# PCB_Sheet1.net
KiCad netlist of a schematic drawn in Altium Designer
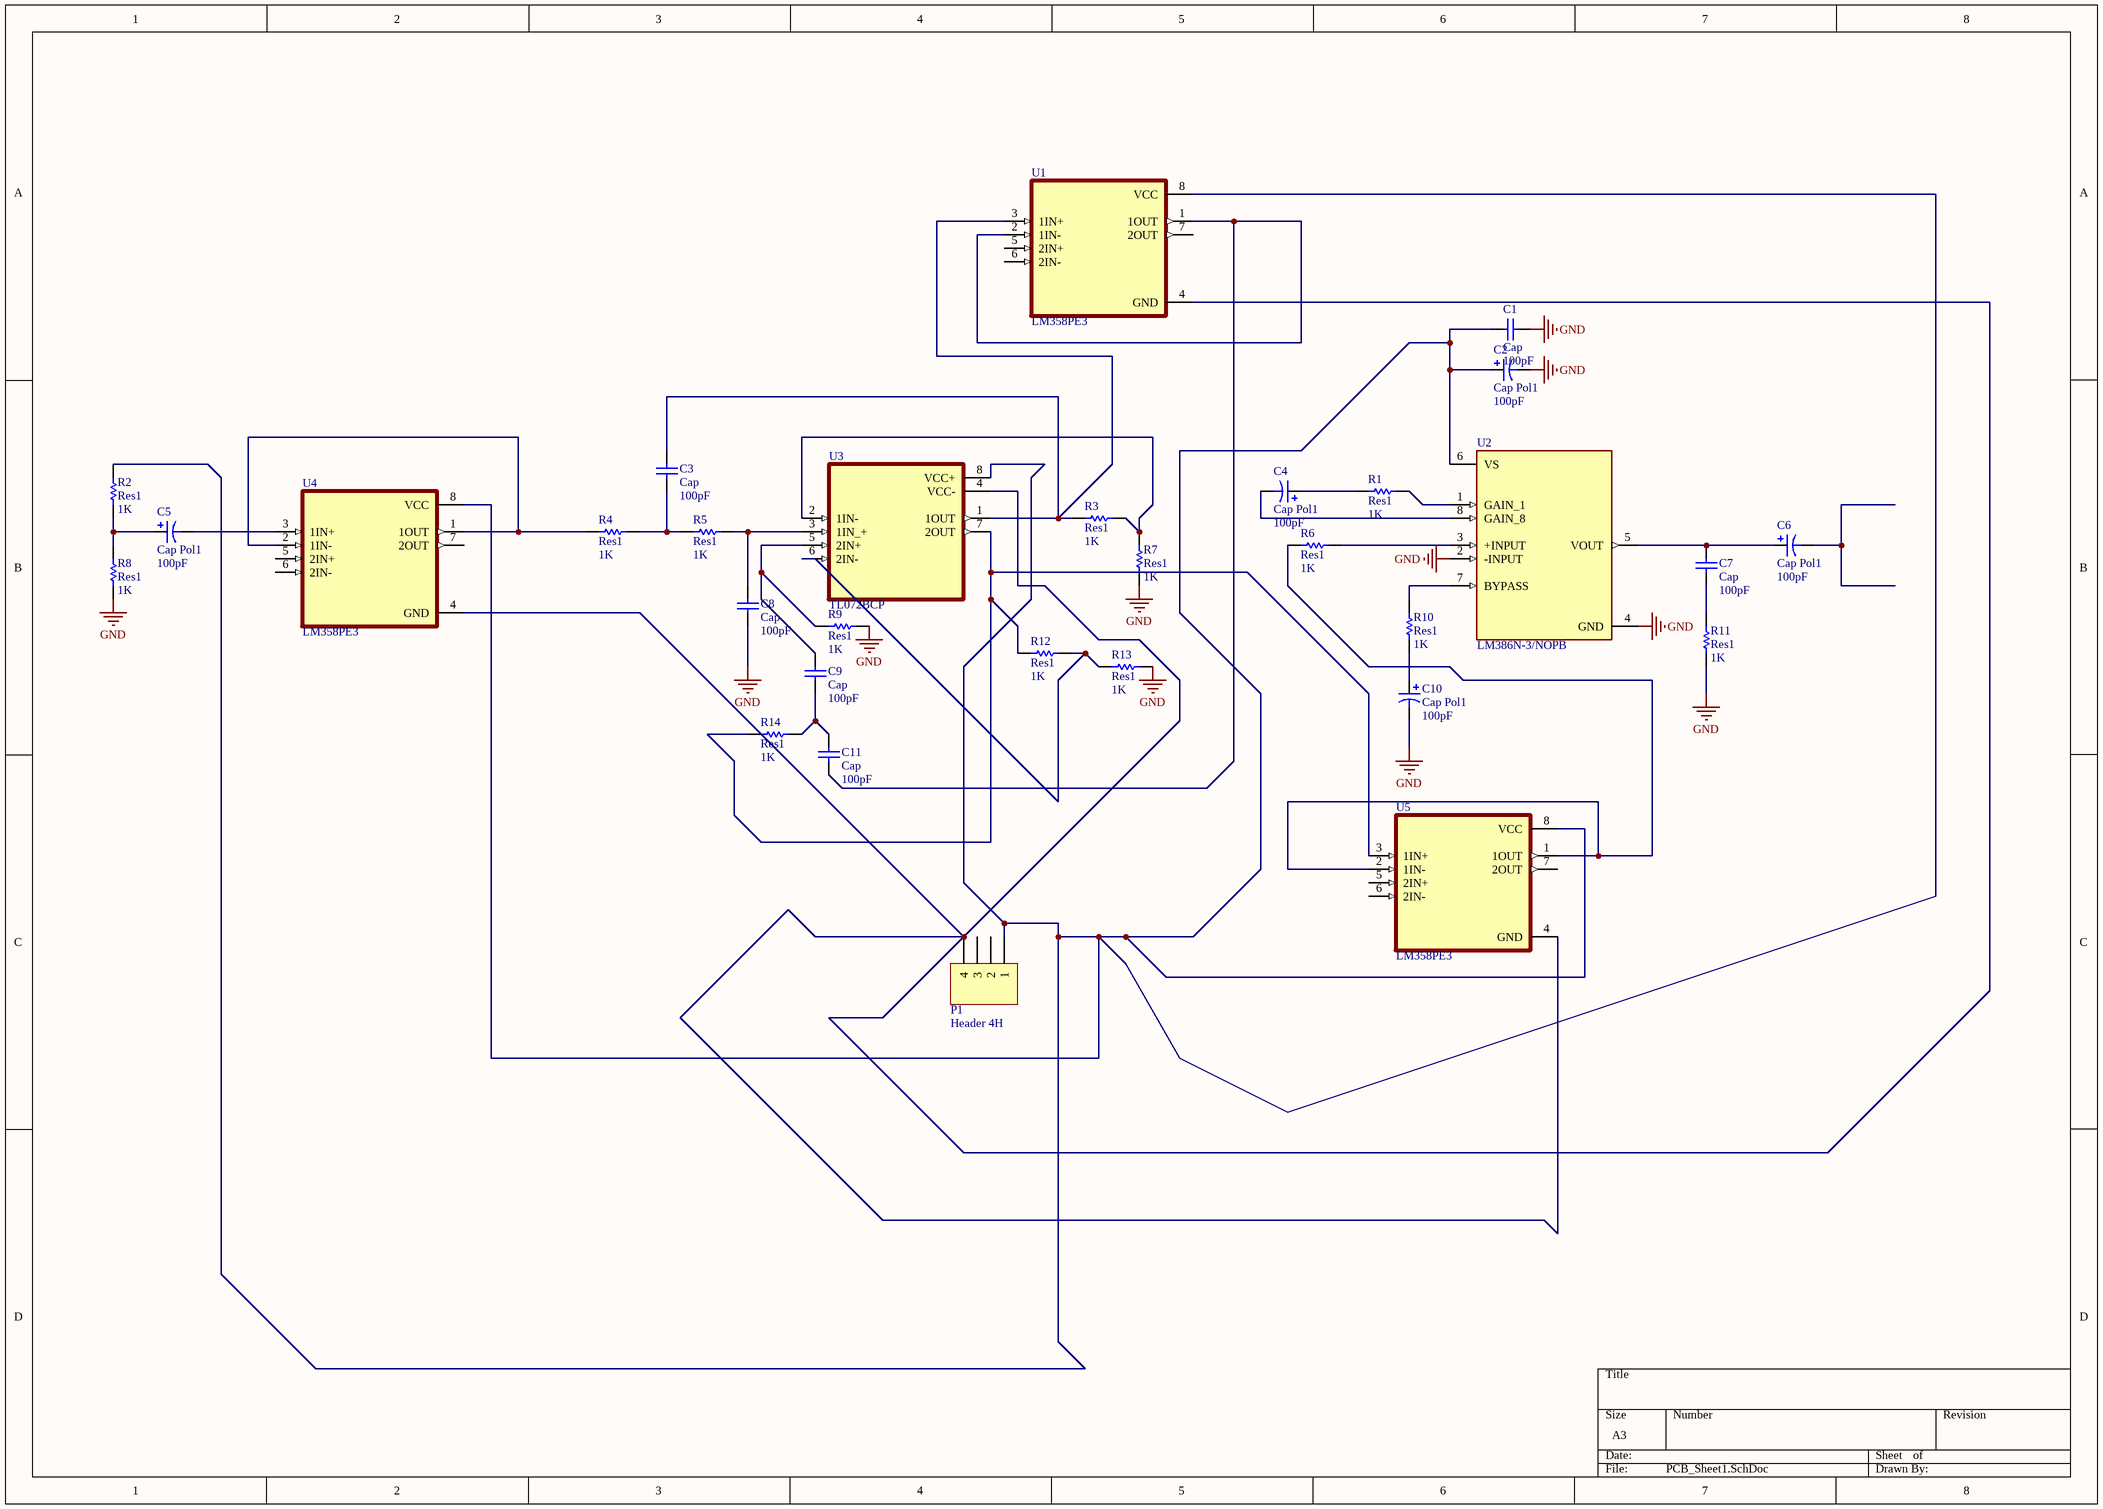
[diagram p0: PCB_Sheet1.SchDoc]

(export (version "E")
  (design (tool "Eeschema 10.0.6"))
  (components
    (comp (ref "C1")
      (value "Cap")
      (footprint "RAD-0.3")
      (description "Capacitor")
      (fields (field (name "ALTIUM_VALUE") "100pF") (field (name "PUBLISHER") "Altium Limited"))
      (libsource (lib "Miscellaneous_Devices") (part "Cap"))
    )
    (comp (ref "C2")
      (value "Cap Pol1")
      (footprint "RB7.6-15")
      (description "Polarized Capacitor (Radial)")
      (fields (field (name "ALTIUM_VALUE") "100pF") (field (name "PUBLISHER") "Altium Limited"))
      (libsource (lib "Miscellaneous_Devices") (part "Cap Pol1"))
    )
    (comp (ref "C3")
      (value "Cap")
      (footprint "RAD-0.3")
      (description "Capacitor")
      (fields (field (name "ALTIUM_VALUE") "100pF") (field (name "PUBLISHER") "Altium Limited"))
      (libsource (lib "Miscellaneous_Devices") (part "Cap"))
    )
    (comp (ref "C4")
      (value "Cap Pol1")
      (footprint "RB7.6-15")
      (description "Polarized Capacitor (Radial)")
      (fields (field (name "ALTIUM_VALUE") "100pF") (field (name "PUBLISHER") "Altium Limited"))
      (libsource (lib "Miscellaneous_Devices") (part "Cap Pol1"))
    )
    (comp (ref "C5")
      (value "Cap Pol1")
      (footprint "RB7.6-15")
      (description "Polarized Capacitor (Radial)")
      (fields (field (name "ALTIUM_VALUE") "100pF") (field (name "PUBLISHER") "Altium Limited"))
      (libsource (lib "Miscellaneous_Devices") (part "Cap Pol1"))
    )
    (comp (ref "C6")
      (value "Cap Pol1")
      (footprint "RB7.6-15")
      (description "Polarized Capacitor (Radial)")
      (fields (field (name "ALTIUM_VALUE") "100pF") (field (name "PUBLISHER") "Altium Limited"))
      (libsource (lib "Miscellaneous_Devices") (part "Cap Pol1"))
    )
    (comp (ref "C7")
      (value "Cap")
      (footprint "RAD-0.3")
      (description "Capacitor")
      (fields (field (name "ALTIUM_VALUE") "100pF") (field (name "PUBLISHER") "Altium Limited"))
      (libsource (lib "Miscellaneous_Devices") (part "Cap"))
    )
    (comp (ref "C8")
      (value "Cap")
      (footprint "RAD-0.3")
      (description "Capacitor")
      (fields (field (name "ALTIUM_VALUE") "100pF") (field (name "PUBLISHER") "Altium Limited"))
      (libsource (lib "Miscellaneous_Devices") (part "Cap"))
    )
    (comp (ref "C9")
      (value "Cap")
      (footprint "RAD-0.3")
      (description "Capacitor")
      (fields (field (name "ALTIUM_VALUE") "100pF") (field (name "PUBLISHER") "Altium Limited"))
      (libsource (lib "Miscellaneous_Devices") (part "Cap"))
    )
    (comp (ref "C10")
      (value "Cap Pol1")
      (footprint "RB7.6-15")
      (description "Polarized Capacitor (Radial)")
      (fields (field (name "ALTIUM_VALUE") "100pF") (field (name "PUBLISHER") "Altium Limited"))
      (libsource (lib "Miscellaneous_Devices") (part "Cap Pol1"))
    )
    (comp (ref "C11")
      (value "Cap")
      (footprint "RAD-0.3")
      (description "Capacitor")
      (fields (field (name "ALTIUM_VALUE") "100pF") (field (name "PUBLISHER") "Altium Limited"))
      (libsource (lib "Miscellaneous_Devices") (part "Cap"))
    )
    (comp (ref "P1")
      (value "Header 4H")
      (footprint "HDR1X4H")
      (description "Header, 4-Pin, Right Angle")
      (fields (field (name "PUBLISHER") "Altium Limited"))
      (libsource (lib "Miscellaneous_Connectors") (part "Header 4H"))
    )
    (comp (ref "R1")
      (value "Res1")
      (footprint "AXIAL-0.3")
      (description "Resistor")
      (fields (field (name "ALTIUM_VALUE") "1K") (field (name "PUBLISHER") "Altium Limited"))
      (libsource (lib "Miscellaneous_Devices") (part "Res1"))
    )
    (comp (ref "R2")
      (value "Res1")
      (footprint "AXIAL-0.3")
      (description "Resistor")
      (fields (field (name "ALTIUM_VALUE") "1K") (field (name "PUBLISHER") "Altium Limited"))
      (libsource (lib "Miscellaneous_Devices") (part "Res1"))
    )
    (comp (ref "R3")
      (value "Res1")
      (footprint "AXIAL-0.3")
      (description "Resistor")
      (fields (field (name "ALTIUM_VALUE") "1K") (field (name "PUBLISHER") "Altium Limited"))
      (libsource (lib "Miscellaneous_Devices") (part "Res1"))
    )
    (comp (ref "R4")
      (value "Res1")
      (footprint "AXIAL-0.3")
      (description "Resistor")
      (fields (field (name "ALTIUM_VALUE") "1K") (field (name "PUBLISHER") "Altium Limited"))
      (libsource (lib "Miscellaneous_Devices") (part "Res1"))
    )
    (comp (ref "R5")
      (value "Res1")
      (footprint "AXIAL-0.3")
      (description "Resistor")
      (fields (field (name "ALTIUM_VALUE") "1K") (field (name "PUBLISHER") "Altium Limited"))
      (libsource (lib "Miscellaneous_Devices") (part "Res1"))
    )
    (comp (ref "R6")
      (value "Res1")
      (footprint "AXIAL-0.3")
      (description "Resistor")
      (fields (field (name "ALTIUM_VALUE") "1K") (field (name "PUBLISHER") "Altium Limited"))
      (libsource (lib "Miscellaneous_Devices") (part "Res1"))
    )
    (comp (ref "R7")
      (value "Res1")
      (footprint "AXIAL-0.3")
      (description "Resistor")
      (fields (field (name "ALTIUM_VALUE") "1K") (field (name "PUBLISHER") "Altium Limited"))
      (libsource (lib "Miscellaneous_Devices") (part "Res1"))
    )
    (comp (ref "R8")
      (value "Res1")
      (footprint "AXIAL-0.3")
      (description "Resistor")
      (fields (field (name "ALTIUM_VALUE") "1K") (field (name "PUBLISHER") "Altium Limited"))
      (libsource (lib "Miscellaneous_Devices") (part "Res1"))
    )
    (comp (ref "R9")
      (value "Res1")
      (footprint "AXIAL-0.3")
      (description "Resistor")
      (fields (field (name "ALTIUM_VALUE") "1K") (field (name "PUBLISHER") "Altium Limited"))
      (libsource (lib "Miscellaneous_Devices") (part "Res1"))
    )
    (comp (ref "R10")
      (value "Res1")
      (footprint "AXIAL-0.3")
      (description "Resistor")
      (fields (field (name "ALTIUM_VALUE") "1K") (field (name "PUBLISHER") "Altium Limited"))
      (libsource (lib "Miscellaneous_Devices") (part "Res1"))
    )
    (comp (ref "R11")
      (value "Res1")
      (footprint "AXIAL-0.3")
      (description "Resistor")
      (fields (field (name "ALTIUM_VALUE") "1K") (field (name "PUBLISHER") "Altium Limited"))
      (libsource (lib "Miscellaneous_Devices") (part "Res1"))
    )
    (comp (ref "R12")
      (value "Res1")
      (footprint "AXIAL-0.3")
      (description "Resistor")
      (fields (field (name "ALTIUM_VALUE") "1K") (field (name "PUBLISHER") "Altium Limited"))
      (libsource (lib "Miscellaneous_Devices") (part "Res1"))
    )
    (comp (ref "R13")
      (value "Res1")
      (footprint "AXIAL-0.3")
      (description "Resistor")
      (fields (field (name "ALTIUM_VALUE") "1K") (field (name "PUBLISHER") "Altium Limited"))
      (libsource (lib "Miscellaneous_Devices") (part "Res1"))
    )
    (comp (ref "R14")
      (value "Res1")
      (footprint "AXIAL-0.3")
      (description "Resistor")
      (fields (field (name "ALTIUM_VALUE") "1K") (field (name "PUBLISHER") "Altium Limited"))
      (libsource (lib "Miscellaneous_Devices") (part "Res1"))
    )
    (comp (ref "U1")
      (value "LM358PE3")
      (footprint "DIP794W45P254L959H508Q8")
      (libsource (lib "LM358PE3") (part "LM358PE3"))
    )
    (comp (ref "U2")
      (value "LM386N-3/NOPB")
      (footprint "DIP794W45P254L959H508Q8")
      (libsource (lib "LM386N-3_NOPB") (part "LM386N-3/NOPB"))
    )
    (comp (ref "U3")
      (value "TL072BCP")
      (footprint "DIP794W45P254L959H508Q8")
      (description "Dual low-noise JFET-input low offset operational amplifier 8-PDIP 0 to 70")
      (fields (field (name "MF") "Texas Instruments"))
      (libsource (lib "TL072BCP") (part "TL072BCP"))
    )
    (comp (ref "U4")
      (value "LM358PE3")
      (footprint "DIP794W45P254L959H508Q8")
      (libsource (lib "LM358PE3") (part "LM358PE3"))
    )
    (comp (ref "U5")
      (value "LM358PE3")
      (footprint "DIP794W45P254L959H508Q8")
      (libsource (lib "LM358PE3") (part "LM358PE3"))
    )
  )
  (nets
    (net (code "1") (name "GND") (class "Default")
      (node (ref "C1") (pin "1") (pinfunction "1_1") (pintype "passive"))
      (node (ref "C10") (pin "2") (pinfunction "2_2") (pintype "passive"))
      (node (ref "C2") (pin "2") (pinfunction "2_2") (pintype "passive"))
      (node (ref "C8") (pin "1") (pinfunction "1_1") (pintype "passive"))
      (node (ref "R11") (pin "2") (pinfunction "2_2") (pintype "passive"))
      (node (ref "R13") (pin "1") (pinfunction "1_1") (pintype "passive"))
      (node (ref "R7") (pin "2") (pinfunction "2_2") (pintype "passive"))
      (node (ref "R8") (pin "1") (pinfunction "1_1") (pintype "passive"))
      (node (ref "R9") (pin "1") (pinfunction "1_1") (pintype "passive"))
      (node (ref "U2") (pin "2") (pinfunction "-INPUT_2") (pintype "input"))
      (node (ref "U2") (pin "4") (pinfunction "GND_4") (pintype "power_in"))
    )
    (net (code "2") (name "Net-(C3-Pad1)") (class "Default")
      (node (ref "C3") (pin "1") (pinfunction "1_1") (pintype "passive"))
      (node (ref "R4") (pin "1") (pinfunction "1_1") (pintype "passive"))
      (node (ref "R5") (pin "2") (pinfunction "2_2") (pintype "passive"))
    )
    (net (code "3") (name "Net-(C4-Pad1)") (class "Default")
      (node (ref "C4") (pin "1") (pinfunction "1_1") (pintype "passive"))
      (node (ref "R1") (pin "2") (pinfunction "2_2") (pintype "passive"))
    )
    (net (code "4") (name "Net-(C5-Pad1)") (class "Default")
      (node (ref "C5") (pin "1") (pinfunction "1_1") (pintype "passive"))
      (node (ref "R2") (pin "1") (pinfunction "1_1") (pintype "passive"))
      (node (ref "R8") (pin "2") (pinfunction "2_2") (pintype "passive"))
    )
    (net (code "5") (name "Net-(C7-Pad1)") (class "Default")
      (node (ref "C7") (pin "1") (pinfunction "1_1") (pintype "passive"))
      (node (ref "R11") (pin "1") (pinfunction "1_1") (pintype "passive"))
    )
    (net (code "6") (name "Net-(C10-Pad1)") (class "Default")
      (node (ref "C10") (pin "1") (pinfunction "1_1") (pintype "passive"))
      (node (ref "R10") (pin "2") (pinfunction "2_2") (pintype "passive"))
    )
    (net (code "7") (name "Net-(C11-Pad2)") (class "Default")
      (node (ref "C11") (pin "2") (pinfunction "2_2") (pintype "passive"))
      (node (ref "C9") (pin "1") (pinfunction "1_1") (pintype "passive"))
      (node (ref "R14") (pin "1") (pinfunction "1_1") (pintype "passive"))
    )
    (net (code "8") (name "Net-(U1-1IN+)") (class "Default")
      (node (ref "C3") (pin "2") (pinfunction "2_2") (pintype "passive"))
      (node (ref "R3") (pin "1") (pinfunction "1_1") (pintype "passive"))
      (node (ref "U1") (pin "3") (pinfunction "1IN+_3") (pintype "input"))
      (node (ref "U3") (pin "1") (pinfunction "1OUT_1") (pintype "output"))
    )
    (net (code "9") (name "Net-(U1-1IN-)") (class "Default")
      (node (ref "C11") (pin "1") (pinfunction "1_1") (pintype "passive"))
      (node (ref "U1") (pin "1") (pinfunction "1OUT_1") (pintype "output"))
      (node (ref "U1") (pin "2") (pinfunction "1IN-_2") (pintype "input"))
    )
    (net (code "10") (name "Net-(U1-GND)") (class "Default")
      (node (ref "P1") (pin "4") (pinfunction "4_4") (pintype "passive"))
      (node (ref "U1") (pin "4") (pinfunction "GND_4") (pintype "power_in"))
      (node (ref "U3") (pin "4") (pinfunction "VCC-_4") (pintype "power_in"))
      (node (ref "U4") (pin "4") (pinfunction "GND_4") (pintype "power_in"))
      (node (ref "U5") (pin "4") (pinfunction "GND_4") (pintype "power_in"))
    )
    (net (code "11") (name "Net-(U1-VCC)") (class "Default")
      (node (ref "C1") (pin "2") (pinfunction "2_2") (pintype "passive"))
      (node (ref "C2") (pin "1") (pinfunction "1_1") (pintype "passive"))
      (node (ref "P1") (pin "1") (pinfunction "1_1") (pintype "passive"))
      (node (ref "R2") (pin "2") (pinfunction "2_2") (pintype "passive"))
      (node (ref "U1") (pin "8") (pinfunction "VCC_8") (pintype "power_in"))
      (node (ref "U2") (pin "6") (pinfunction "VS_6") (pintype "power_in"))
      (node (ref "U3") (pin "8") (pinfunction "VCC+_8") (pintype "power_in"))
      (node (ref "U4") (pin "8") (pinfunction "VCC_8") (pintype "power_in"))
      (node (ref "U5") (pin "8") (pinfunction "VCC_8") (pintype "power_in"))
    )
    (net (code "12") (name "Net-(U2-+INPUT)") (class "Default")
      (node (ref "R6") (pin "1") (pinfunction "1_1") (pintype "passive"))
      (node (ref "U2") (pin "3") (pinfunction "+INPUT_3") (pintype "input"))
    )
    (net (code "13") (name "Net-(U2-BYPASS)") (class "Default")
      (node (ref "R10") (pin "1") (pinfunction "1_1") (pintype "passive"))
      (node (ref "U2") (pin "7") (pinfunction "BYPASS_7") (pintype "input"))
    )
    (net (code "14") (name "Net-(U2-GAIN_1)") (class "Default")
      (node (ref "R1") (pin "1") (pinfunction "1_1") (pintype "passive"))
      (node (ref "U2") (pin "1") (pinfunction "GAIN_1_1") (pintype "input"))
    )
    (net (code "15") (name "Net-(U2-GAIN_8)") (class "Default")
      (node (ref "C4") (pin "2") (pinfunction "2_2") (pintype "passive"))
      (node (ref "U2") (pin "8") (pinfunction "GAIN_8_8") (pintype "input"))
    )
    (net (code "16") (name "Net-(U2-VOUT)") (class "Default")
      (node (ref "C6") (pin "1") (pinfunction "1_1") (pintype "passive"))
      (node (ref "C7") (pin "2") (pinfunction "2_2") (pintype "passive"))
      (node (ref "U2") (pin "5") (pinfunction "VOUT_5") (pintype "output"))
    )
    (net (code "17") (name "Net-(U3-1IN-)") (class "Default")
      (node (ref "R3") (pin "2") (pinfunction "2_2") (pintype "passive"))
      (node (ref "R7") (pin "1") (pinfunction "1_1") (pintype "passive"))
      (node (ref "U3") (pin "2") (pinfunction "1IN-_2") (pintype "input"))
    )
    (net (code "18") (name "Net-(U3-1IN_+)") (class "Default")
      (node (ref "C8") (pin "2") (pinfunction "2_2") (pintype "passive"))
      (node (ref "R5") (pin "1") (pinfunction "1_1") (pintype "passive"))
      (node (ref "U3") (pin "3") (pinfunction "1IN_+_3") (pintype "input"))
    )
    (net (code "19") (name "Net-(U3-2IN+)") (class "Default")
      (node (ref "C9") (pin "2") (pinfunction "2_2") (pintype "passive"))
      (node (ref "R9") (pin "2") (pinfunction "2_2") (pintype "passive"))
      (node (ref "U3") (pin "5") (pinfunction "2IN+_5") (pintype "input"))
    )
    (net (code "20") (name "Net-(U3-2IN-)") (class "Default")
      (node (ref "R12") (pin "1") (pinfunction "1_1") (pintype "passive"))
      (node (ref "R13") (pin "2") (pinfunction "2_2") (pintype "passive"))
      (node (ref "U3") (pin "6") (pinfunction "2IN-_6") (pintype "input"))
    )
    (net (code "21") (name "Net-(U3-2OUT)") (class "Default")
      (node (ref "R12") (pin "2") (pinfunction "2_2") (pintype "passive"))
      (node (ref "R14") (pin "2") (pinfunction "2_2") (pintype "passive"))
      (node (ref "U3") (pin "7") (pinfunction "2OUT_7") (pintype "output"))
      (node (ref "U5") (pin "3") (pinfunction "1IN+_3") (pintype "input"))
    )
    (net (code "22") (name "Net-(U4-1IN+)") (class "Default")
      (node (ref "C5") (pin "2") (pinfunction "2_2") (pintype "passive"))
      (node (ref "U4") (pin "3") (pinfunction "1IN+_3") (pintype "input"))
    )
    (net (code "23") (name "Net-(U4-1IN-)") (class "Default")
      (node (ref "R4") (pin "2") (pinfunction "2_2") (pintype "passive"))
      (node (ref "U4") (pin "1") (pinfunction "1OUT_1") (pintype "output"))
      (node (ref "U4") (pin "2") (pinfunction "1IN-_2") (pintype "input"))
    )
    (net (code "24") (name "Net-(U5-1IN-)") (class "Default")
      (node (ref "R6") (pin "2") (pinfunction "2_2") (pintype "passive"))
      (node (ref "U5") (pin "1") (pinfunction "1OUT_1") (pintype "output"))
      (node (ref "U5") (pin "2") (pinfunction "1IN-_2") (pintype "input"))
    )
    (net (code "25") (name "unconnected-(C6-Pad2)") (class "Default")
      (node (ref "C6") (pin "2") (pinfunction "2_2") (pintype "passive"))
    )
    (net (code "26") (name "unconnected-(P1-Pad2)") (class "Default")
      (node (ref "P1") (pin "2") (pinfunction "2_2") (pintype "passive"))
    )
    (net (code "27") (name "unconnected-(P1-Pad3)") (class "Default")
      (node (ref "P1") (pin "3") (pinfunction "3_3") (pintype "passive"))
    )
    (net (code "28") (name "unconnected-(U1-2IN+-Pad5)") (class "Default")
      (node (ref "U1") (pin "5") (pinfunction "2IN+_5") (pintype "input"))
    )
    (net (code "29") (name "unconnected-(U1-2IN--Pad6)") (class "Default")
      (node (ref "U1") (pin "6") (pinfunction "2IN-_6") (pintype "input"))
    )
    (net (code "30") (name "unconnected-(U1-2OUT-Pad7)") (class "Default")
      (node (ref "U1") (pin "7") (pinfunction "2OUT_7") (pintype "output"))
    )
    (net (code "31") (name "unconnected-(U4-2IN+-Pad5)") (class "Default")
      (node (ref "U4") (pin "5") (pinfunction "2IN+_5") (pintype "input"))
    )
    (net (code "32") (name "unconnected-(U4-2IN--Pad6)") (class "Default")
      (node (ref "U4") (pin "6") (pinfunction "2IN-_6") (pintype "input"))
    )
    (net (code "33") (name "unconnected-(U4-2OUT-Pad7)") (class "Default")
      (node (ref "U4") (pin "7") (pinfunction "2OUT_7") (pintype "output"))
    )
    (net (code "34") (name "unconnected-(U5-2IN+-Pad5)") (class "Default")
      (node (ref "U5") (pin "5") (pinfunction "2IN+_5") (pintype "input"))
    )
    (net (code "35") (name "unconnected-(U5-2IN--Pad6)") (class "Default")
      (node (ref "U5") (pin "6") (pinfunction "2IN-_6") (pintype "input"))
    )
    (net (code "36") (name "unconnected-(U5-2OUT-Pad7)") (class "Default")
      (node (ref "U5") (pin "7") (pinfunction "2OUT_7") (pintype "output"))
    )
  )
)
